# targetboard2.net
KiCad netlist of a schematic drawn in EAGLE
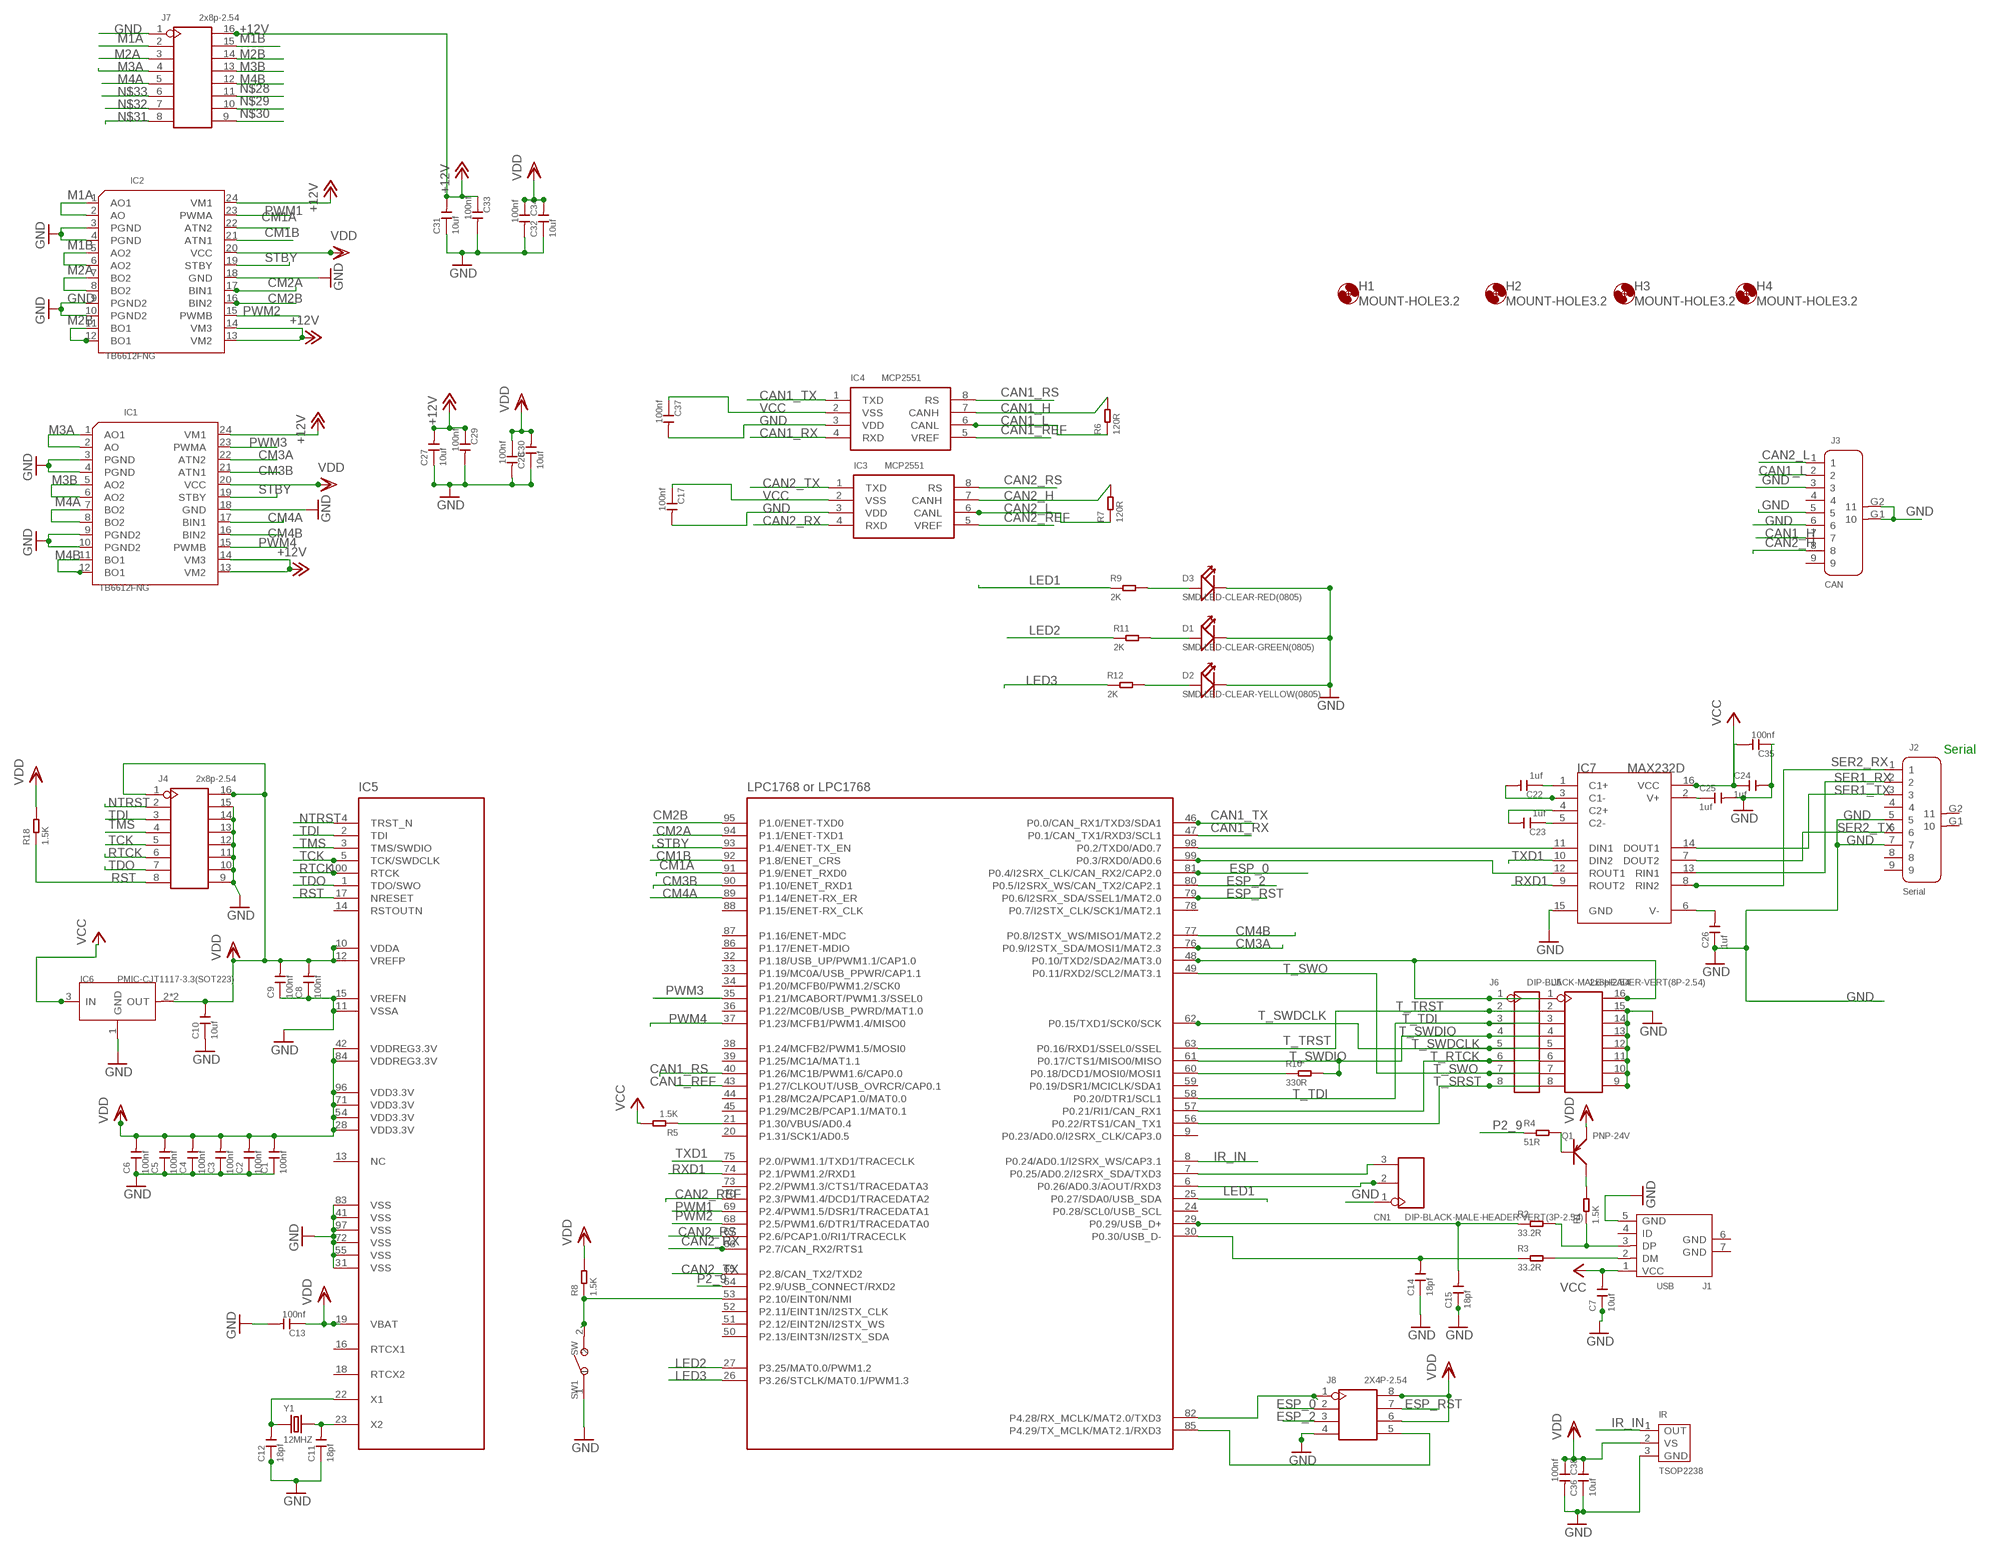
[diagram p0: schematic, sheet 1]

(export (version "E")
  (design (tool "Eeschema 10.0.6"))
  (components
    (comp (ref "C1")
      (value "100nf")
      (footprint "eagle-import:C0805")
      (fields (field (name "MPN") "CC0805KRX7R9BB104"))
      (libsource (lib "eagle-import") (part "CERAMIC-100NF-50V-10%-X7R(0805)"))
    )
    (comp (ref "C2")
      (value "100nf")
      (footprint "eagle-import:C0805")
      (fields (field (name "MPN") "CC0805KRX7R9BB104"))
      (libsource (lib "eagle-import") (part "CERAMIC-100NF-50V-10%-X7R(0805)"))
    )
    (comp (ref "C3")
      (value "100nf")
      (footprint "eagle-import:C0805")
      (fields (field (name "MPN") "CC0805KRX7R9BB104"))
      (libsource (lib "eagle-import") (part "CERAMIC-100NF-50V-10%-X7R(0805)"))
    )
    (comp (ref "C4")
      (value "100nf")
      (footprint "eagle-import:C0805")
      (fields (field (name "MPN") "CC0805KRX7R9BB104"))
      (libsource (lib "eagle-import") (part "CERAMIC-100NF-50V-10%-X7R(0805)"))
    )
    (comp (ref "C5")
      (value "100nf")
      (footprint "eagle-import:C0805")
      (fields (field (name "MPN") "CC0805KRX7R9BB104"))
      (libsource (lib "eagle-import") (part "CERAMIC-100NF-50V-10%-X7R(0805)"))
    )
    (comp (ref "C6")
      (value "100nf")
      (footprint "eagle-import:C0805")
      (fields (field (name "MPN") "CC0805KRX7R9BB104"))
      (libsource (lib "eagle-import") (part "CERAMIC-100NF-50V-10%-X7R(0805)"))
    )
    (comp (ref "C7")
      (value "10uf")
      (footprint "eagle-import:C0603")
      (fields (field (name "MPN") "CC0603KRX5R6BB106"))
      (libsource (lib "eagle-import") (part "CERAMIC-10UF-10V-10%-X5R(0603)"))
    )
    (comp (ref "C8")
      (value "100nf")
      (footprint "eagle-import:C0805")
      (fields (field (name "MPN") "CC0805KRX7R9BB104"))
      (libsource (lib "eagle-import") (part "CERAMIC-100NF-50V-10%-X7R(0805)"))
    )
    (comp (ref "C9")
      (value "100nf")
      (footprint "eagle-import:C0805")
      (fields (field (name "MPN") "CC0805KRX7R9BB104"))
      (libsource (lib "eagle-import") (part "CERAMIC-100NF-50V-10%-X7R(0805)"))
    )
    (comp (ref "C10")
      (value "10uf")
      (footprint "eagle-import:C0805")
      (fields (field (name "MPN") "CC0805KKX5R8BB106"))
      (libsource (lib "eagle-import") (part "CERAMIC-10UF-25V-10%-X5R(0805)"))
    )
    (comp (ref "C11")
      (value "18pf")
      (footprint "eagle-import:C0805")
      (libsource (lib "eagle-import") (part "CERAMIC-18PF-50V-5%-NPO(0805)"))
    )
    (comp (ref "C12")
      (value "18pf")
      (footprint "eagle-import:C0805")
      (libsource (lib "eagle-import") (part "CERAMIC-18PF-50V-5%-NPO(0805)"))
    )
    (comp (ref "C13")
      (value "100nf")
      (footprint "eagle-import:C0805")
      (fields (field (name "MPN") "CC0805KRX7R9BB104"))
      (libsource (lib "eagle-import") (part "CERAMIC-100NF-50V-10%-X7R(0805)"))
    )
    (comp (ref "C14")
      (value "18pf")
      (footprint "eagle-import:C0805")
      (libsource (lib "eagle-import") (part "CERAMIC-18PF-50V-5%-NPO(0805)"))
    )
    (comp (ref "C15")
      (value "18pf")
      (footprint "eagle-import:C0805")
      (libsource (lib "eagle-import") (part "CERAMIC-18PF-50V-5%-NPO(0805)"))
    )
    (comp (ref "C17")
      (value "100nf")
      (footprint "eagle-import:C0805")
      (fields (field (name "MPN") "CC0805KRX7R9BB104"))
      (libsource (lib "eagle-import") (part "CERAMIC-100NF-50V-10%-X7R(0805)"))
    )
    (comp (ref "C22")
      (value "1uf")
      (footprint "eagle-import:C0805")
      (fields (field (name "MPN") "CC0805KKX7R8BB105"))
      (libsource (lib "eagle-import") (part "CERAMIC-1UF-25V-10%-X7R(0805)"))
    )
    (comp (ref "C23")
      (value "1uf")
      (footprint "eagle-import:C0805")
      (fields (field (name "MPN") "CC0805KKX7R8BB105"))
      (libsource (lib "eagle-import") (part "CERAMIC-1UF-25V-10%-X7R(0805)"))
    )
    (comp (ref "C24")
      (value "1uf")
      (footprint "eagle-import:C0805")
      (fields (field (name "MPN") "CC0805KKX7R8BB105"))
      (libsource (lib "eagle-import") (part "CERAMIC-1UF-25V-10%-X7R(0805)"))
    )
    (comp (ref "C25")
      (value "1uf")
      (footprint "eagle-import:C0805")
      (fields (field (name "MPN") "CC0805KKX7R8BB105"))
      (libsource (lib "eagle-import") (part "CERAMIC-1UF-25V-10%-X7R(0805)"))
    )
    (comp (ref "C26")
      (value "1uf")
      (footprint "eagle-import:C0805")
      (fields (field (name "MPN") "CC0805KKX7R8BB105"))
      (libsource (lib "eagle-import") (part "CERAMIC-1UF-25V-10%-X7R(0805)"))
    )
    (comp (ref "C27")
      (value "10uf")
      (footprint "eagle-import:C0805")
      (fields (field (name "MPN") "CC0805KKX5R8BB106"))
      (libsource (lib "eagle-import") (part "CERAMIC-10UF-25V-10%-X5R(0805)"))
    )
    (comp (ref "C28")
      (value "10uf")
      (footprint "eagle-import:C0805")
      (fields (field (name "MPN") "CC0805KKX5R8BB106"))
      (libsource (lib "eagle-import") (part "CERAMIC-10UF-25V-10%-X5R(0805)"))
    )
    (comp (ref "C29")
      (value "100nf")
      (footprint "eagle-import:C0805")
      (fields (field (name "MPN") "CC0805KRX7R9BB104"))
      (libsource (lib "eagle-import") (part "CERAMIC-100NF-50V-10%-X7R(0805)"))
    )
    (comp (ref "C30")
      (value "100nf")
      (footprint "eagle-import:C0805")
      (fields (field (name "MPN") "CC0805KRX7R9BB104"))
      (libsource (lib "eagle-import") (part "CERAMIC-100NF-50V-10%-X7R(0805)"))
    )
    (comp (ref "C31")
      (value "10uf")
      (footprint "eagle-import:C0805")
      (fields (field (name "MPN") "CC0805KKX5R8BB106"))
      (libsource (lib "eagle-import") (part "CERAMIC-10UF-25V-10%-X5R(0805)"))
    )
    (comp (ref "C32")
      (value "10uf")
      (footprint "eagle-import:C0805")
      (fields (field (name "MPN") "CC0805KKX5R8BB106"))
      (libsource (lib "eagle-import") (part "CERAMIC-10UF-25V-10%-X5R(0805)"))
    )
    (comp (ref "C33")
      (value "100nf")
      (footprint "eagle-import:C0805")
      (fields (field (name "MPN") "CC0805KRX7R9BB104"))
      (libsource (lib "eagle-import") (part "CERAMIC-100NF-50V-10%-X7R(0805)"))
    )
    (comp (ref "C34")
      (value "100nf")
      (footprint "eagle-import:C0805")
      (fields (field (name "MPN") "CC0805KRX7R9BB104"))
      (libsource (lib "eagle-import") (part "CERAMIC-100NF-50V-10%-X7R(0805)"))
    )
    (comp (ref "C35")
      (value "100nf")
      (footprint "eagle-import:C0805")
      (fields (field (name "MPN") "CC0805KRX7R9BB104"))
      (libsource (lib "eagle-import") (part "CERAMIC-100NF-50V-10%-X7R(0805)"))
    )
    (comp (ref "C36")
      (value "10uf")
      (footprint "eagle-import:C0805")
      (fields (field (name "MPN") "CC0805KKX5R8BB106"))
      (libsource (lib "eagle-import") (part "CERAMIC-10UF-25V-10%-X5R(0805)"))
    )
    (comp (ref "C37")
      (value "100nf")
      (footprint "eagle-import:C0805")
      (fields (field (name "MPN") "CC0805KRX7R9BB104"))
      (libsource (lib "eagle-import") (part "CERAMIC-100NF-50V-10%-X7R(0805)"))
    )
    (comp (ref "C38")
      (value "100nf")
      (footprint "eagle-import:C0805")
      (fields (field (name "MPN") "CC0805KRX7R9BB104"))
      (libsource (lib "eagle-import") (part "CERAMIC-100NF-50V-10%-X7R(0805)"))
    )
    (comp (ref "CN1")
      (value "DIP-BLACK-MALE-HEADER-VERT(3P-2.54)")
      (footprint "eagle-import:H3-2.54")
      (libsource (lib "eagle-import") (part "DIP-BLACK-MALE-HEADER-VERT(3P-2.54)"))
    )
    (comp (ref "D1")
      (value "SMD-LED-CLEAR-GREEN(0805)")
      (footprint "eagle-import:LED-0805")
      (fields (field (name "MPN") "17-215SYGC/S530-E2/TR8"))
      (libsource (lib "eagle-import") (part "SMD-LED-CLEAR-GREEN(0805)"))
    )
    (comp (ref "D2")
      (value "SMD-LED-CLEAR-YELLOW(0805)")
      (footprint "eagle-import:LED-0805")
      (fields (field (name "MPN") "17-215UYC/S530-A3/TR8"))
      (libsource (lib "eagle-import") (part "SMD-LED-CLEAR-YELLOW(0805)"))
    )
    (comp (ref "D3")
      (value "SMD-LED-CLEAR-RED(0805)")
      (footprint "eagle-import:LED-0805")
      (fields (field (name "MPN") "17-215SURC/S530-A2/TR8"))
      (libsource (lib "eagle-import") (part "SMD-LED-CLEAR-RED(0805)"))
    )
    (comp (ref "H1")
      (value "MOUNT-HOLE3.2")
      (footprint "eagle-import:3,2")
      (libsource (lib "eagle-import") (part "MOUNT-HOLE3.2"))
    )
    (comp (ref "H2")
      (value "MOUNT-HOLE3.2")
      (footprint "eagle-import:3,2")
      (libsource (lib "eagle-import") (part "MOUNT-HOLE3.2"))
    )
    (comp (ref "H3")
      (value "MOUNT-HOLE3.2")
      (footprint "eagle-import:3,2")
      (libsource (lib "eagle-import") (part "MOUNT-HOLE3.2"))
    )
    (comp (ref "H4")
      (value "MOUNT-HOLE3.2")
      (footprint "eagle-import:3,2")
      (libsource (lib "eagle-import") (part "MOUNT-HOLE3.2"))
    )
    (comp (ref "IC1")
      (value "TB6612FNG")
      (footprint "eagle-import:SSOP24-0.65-8.9X5.3MM")
      (fields (field (name "MPN") "TB6612FNG-O/C8/EL"))
      (libsource (lib "eagle-import") (part "DRIVER-TB6612FNG-O/C8/EL(SSOP24)"))
    )
    (comp (ref "IC2")
      (value "TB6612FNG")
      (footprint "eagle-import:SSOP24-0.65-8.9X5.3MM")
      (fields (field (name "MPN") "TB6612FNG-O/C8/EL"))
      (libsource (lib "eagle-import") (part "DRIVER-TB6612FNG-O/C8/EL(SSOP24)"))
    )
    (comp (ref "IC3")
      (value "MCP2551")
      (footprint "eagle-import:SOIC8-1.27-5X4MM")
      (fields (field (name "MPN") "MCP2551-I/SN"))
      (libsource (lib "eagle-import") (part "INTERFACE-MCP2551-I/SN(SOIC8)"))
    )
    (comp (ref "IC4")
      (value "MCP2551")
      (footprint "eagle-import:SOIC8-1.27-5X4MM")
      (fields (field (name "MPN") "MCP2551-I/SN"))
      (libsource (lib "eagle-import") (part "INTERFACE-MCP2551-I/SN(SOIC8)"))
    )
    (comp (ref "IC5")
      (value "LPC1768 or LPC1768")
      (footprint "eagle-import:LQFP100-0.5-13.8X13.8MM")
      (fields (field (name "MPN") "LPC1768FBD100"))
      (libsource (lib "eagle-import") (part "MCU_LPC1768FBD100(LQFP100)"))
    )
    (comp (ref "IC6")
      (value "PMIC-CJT1117-3.3(SOT223)")
      (footprint "eagle-import:SOT-223")
      (fields (field (name "MPN") "CJT1117-3.3"))
      (libsource (lib "eagle-import") (part "PMIC-CJT1117-3.3(SOT223)"))
    )
    (comp (ref "IC7")
      (value "MAX232D")
      (footprint "eagle-import:SOIC16-1.27-10X3.9MM")
      (libsource (lib "eagle-import") (part "RECEIVER-MAX232D(SOIC16)"))
    )
    (comp (ref "IR")
      (value "TSOP2238")
      (footprint "eagle-import:SNR3-2.54-6.95X6.0X5.6MM")
      (libsource (lib "eagle-import") (part "OPTICAL-TSOP2238"))
    )
    (comp (ref "J1")
      (value "USB")
      (footprint "eagle-import:MICRO-USB5+2P-SMD-0.65")
      (fields (field (name "MPN") "ST-USB-001L"))
      (libsource (lib "eagle-import") (part "MICRO-USB-SMD-TYPE-AB-R/A(ST-USB-001L)"))
    )
    (comp (ref "J2")
      (value "Serial")
      (footprint "eagle-import:DSUB9+2P-2.77-90D-MALE")
      (libsource (lib "eagle-import") (part "DIP-MALE-DB9-CONNECTOR"))
    )
    (comp (ref "J3")
      (value "CAN")
      (footprint "eagle-import:DSUB9+2P-2.77-90D-MALE")
      (libsource (lib "eagle-import") (part "DIP-MALE-DB9-CONNECTOR"))
    )
    (comp (ref "J4")
      (value "2x8p-2.54")
      (footprint "eagle-import:H2X8-2.54")
      (fields (field (name "MPN") "P125-1216A0AS116A1"))
      (libsource (lib "eagle-import") (part "DIP-BLACK-MALE-HEADER-VERT(2X8P-2.54)"))
    )
    (comp (ref "J5")
      (value "2x8p-2.54")
      (footprint "eagle-import:H2X8-2.54")
      (fields (field (name "MPN") "P125-1216A0AS116A1"))
      (libsource (lib "eagle-import") (part "DIP-BLACK-MALE-HEADER-VERT(2X8P-2.54)"))
    )
    (comp (ref "J6")
      (value "DIP-BLACK-MALE-HEADER-VERT(8P-2.54)")
      (footprint "eagle-import:H8-2.54")
      (fields (field (name "MPN") "P125-1108A1BS116A1"))
      (libsource (lib "eagle-import") (part "DIP-BLACK-MALE-HEADER-VERT(8P-2.54)"))
    )
    (comp (ref "J7")
      (value "2x8p-2.54")
      (footprint "eagle-import:H2X8-2.54")
      (fields (field (name "MPN") "P125-1216A0AS116A1"))
      (libsource (lib "eagle-import") (part "DIP-BLACK-MALE-HEADER-VERT(2X8P-2.54)"))
    )
    (comp (ref "J8")
      (value "2X4P-2.54")
      (footprint "eagle-import:H2X4-2.54")
      (libsource (lib "eagle-import") (part "DIP-BLACK-FEMALE-HEADER(2X4P-2.54)"))
    )
    (comp (ref "Q1")
      (value "PNP-24V")
      (footprint "eagle-import:SOT-23")
      (fields (field (name "MPN") "S8550"))
      (libsource (lib "eagle-import") (part "SMD-TRANSISTORS-PNP-25V-500MA(SOT-23)"))
    )
    (comp (ref "R1")
      (value "1.5K")
      (footprint "eagle-import:R0402")
      (fields (field (name "MPN") "RC0402JR-071K5L"))
      (libsource (lib "eagle-import") (part "SMD-RES-1.5K-5%-1/16W(0402)"))
    )
    (comp (ref "R2")
      (value "33.2R")
      (footprint "eagle-import:R0603")
      (fields (field (name "MPN") "RC0603FR-0733R2L"))
      (libsource (lib "eagle-import") (part "SMD-RES-33.2R-1%-1/10W(0603)"))
    )
    (comp (ref "R3")
      (value "33.2R")
      (footprint "eagle-import:R0603")
      (fields (field (name "MPN") "RC0603FR-0733R2L"))
      (libsource (lib "eagle-import") (part "SMD-RES-33.2R-1%-1/10W(0603)"))
    )
    (comp (ref "R4")
      (value "51R")
      (footprint "eagle-import:R0603")
      (fields (field (name "MPN") "RC0603FR-0751RL"))
      (libsource (lib "eagle-import") (part "SMD-RES-51R-1%-1/10W(0603)"))
    )
    (comp (ref "R5")
      (value "1.5K")
      (footprint "eagle-import:R0402")
      (fields (field (name "MPN") "RC0402JR-071K5L"))
      (libsource (lib "eagle-import") (part "SMD-RES-1.5K-5%-1/16W(0402)"))
    )
    (comp (ref "R6")
      (value "120R")
      (footprint "eagle-import:R0805")
      (fields (field (name "MPN") "RC0805JR-07120RL"))
      (libsource (lib "eagle-import") (part "SMD-RES-120R-5%-1/8W(0805)"))
    )
    (comp (ref "R7")
      (value "120R")
      (footprint "eagle-import:R0805")
      (fields (field (name "MPN") "RC0805JR-07120RL"))
      (libsource (lib "eagle-import") (part "SMD-RES-120R-5%-1/8W(0805)"))
    )
    (comp (ref "R8")
      (value "1.5K")
      (footprint "eagle-import:R0402")
      (fields (field (name "MPN") "RC0402JR-071K5L"))
      (libsource (lib "eagle-import") (part "SMD-RES-1.5K-5%-1/16W(0402)"))
    )
    (comp (ref "R9")
      (value "2K")
      (footprint "eagle-import:R0805")
      (fields (field (name "MPN") "RC0805JR-072KL"))
      (libsource (lib "eagle-import") (part "SMD-RES-2K-5%-1/8W(0805)"))
    )
    (comp (ref "R10")
      (value "330R")
      (footprint "eagle-import:R0603")
      (fields (field (name "MPN") "RC0603FR-07330RL"))
      (libsource (lib "eagle-import") (part "SMD-RES-330R-1%-1/10W(0603)"))
    )
    (comp (ref "R11")
      (value "2K")
      (footprint "eagle-import:R0805")
      (fields (field (name "MPN") "RC0805JR-072KL"))
      (libsource (lib "eagle-import") (part "SMD-RES-2K-5%-1/8W(0805)"))
    )
    (comp (ref "R12")
      (value "2K")
      (footprint "eagle-import:R0805")
      (fields (field (name "MPN") "RC0805JR-072KL"))
      (libsource (lib "eagle-import") (part "SMD-RES-2K-5%-1/8W(0805)"))
    )
    (comp (ref "R18")
      (value "1.5K")
      (footprint "eagle-import:R0402")
      (fields (field (name "MPN") "RC0402JR-071K5L"))
      (libsource (lib "eagle-import") (part "SMD-RES-1.5K-5%-1/16W(0402)"))
    )
    (comp (ref "SW1")
      (value "SW")
      (footprint "eagle-import:SW2-2.6-3.0X2.5X1.2+0.4MM")
      (libsource (lib "eagle-import") (part "SMD-BUTTON(2P-3.0X2.5X1.2+0.4MM)-B3U-1000P-2P-SMD"))
    )
    (comp (ref "Y1")
      (value "12MHZ")
      (footprint "eagle-import:X2-SMD-5.0X3.2X1.3MM")
      (fields (field (name "MPN") "5032/2P"))
      (libsource (lib "eagle-import") (part "SMD-CRYSTAL-12MHZ-20PF-20PPM-40R(2P-5.0X3.2MM)"))
    )
  )
  (nets
    (net (code "1") (name "+12V") (class "Default")
      (node (ref "C27") (pin "2") (pinfunction "2_2") (pintype "passive"))
      (node (ref "C29") (pin "1") (pinfunction "1_1") (pintype "passive"))
      (node (ref "C31") (pin "2") (pinfunction "2_2") (pintype "passive"))
      (node (ref "C33") (pin "1") (pinfunction "1_1") (pintype "passive"))
      (node (ref "IC1") (pin "13") (pinfunction "VM2_13") (pintype "bidirectional"))
      (node (ref "IC1") (pin "14") (pinfunction "VM3_14") (pintype "bidirectional"))
      (node (ref "IC1") (pin "24") (pinfunction "VM1_24") (pintype "bidirectional"))
      (node (ref "IC2") (pin "13") (pinfunction "VM2_13") (pintype "bidirectional"))
      (node (ref "IC2") (pin "14") (pinfunction "VM3_14") (pintype "bidirectional"))
      (node (ref "IC2") (pin "24") (pinfunction "VM1_24") (pintype "bidirectional"))
      (node (ref "J7") (pin "16") (pinfunction "16_16") (pintype "bidirectional"))
    )
    (net (code "2") (name "/CAN1_H") (class "Default")
      (node (ref "IC4") (pin "7") (pinfunction "CANH_7") (pintype "bidirectional"))
      (node (ref "J3") (pin "7") (pinfunction "7_7") (pintype "bidirectional"))
      (node (ref "R6") (pin "2") (pinfunction "2_2") (pintype "passive"))
    )
    (net (code "3") (name "/CAN1_L") (class "Default")
      (node (ref "IC4") (pin "6") (pinfunction "CANL_6") (pintype "bidirectional"))
      (node (ref "J3") (pin "2") (pinfunction "2_2") (pintype "bidirectional"))
      (node (ref "R6") (pin "1") (pinfunction "1_1") (pintype "passive"))
    )
    (net (code "4") (name "/CAN1_REF") (class "Default")
      (node (ref "IC4") (pin "5") (pinfunction "VREF_5") (pintype "bidirectional"))
      (node (ref "IC5") (pin "43") (pinfunction "P1.27/CLKOUT/USB_OVRCR/CAP0.1_43") (pintype "bidirectional"))
    )
    (net (code "5") (name "/CAN1_RS") (class "Default")
      (node (ref "IC4") (pin "8") (pinfunction "RS_8") (pintype "bidirectional"))
      (node (ref "IC5") (pin "40") (pinfunction "P1.26/MC1B/PWM1.6/CAP0.0_40") (pintype "bidirectional"))
    )
    (net (code "6") (name "/CAN1_RX") (class "Default")
      (node (ref "IC4") (pin "4") (pinfunction "RXD_4") (pintype "bidirectional"))
      (node (ref "IC5") (pin "47") (pinfunction "P0.1/CAN_TX1/RXD3/SCL1_47") (pintype "bidirectional"))
    )
    (net (code "7") (name "/CAN1_TX") (class "Default")
      (node (ref "IC4") (pin "1") (pinfunction "TXD_1") (pintype "bidirectional"))
      (node (ref "IC5") (pin "46") (pinfunction "P0.0/CAN_RX1/TXD3/SDA1_46") (pintype "bidirectional"))
    )
    (net (code "8") (name "/CAN2_H") (class "Default")
      (node (ref "IC3") (pin "7") (pinfunction "CANH_7") (pintype "bidirectional"))
      (node (ref "J3") (pin "8") (pinfunction "8_8") (pintype "bidirectional"))
      (node (ref "R7") (pin "2") (pinfunction "2_2") (pintype "passive"))
    )
    (net (code "9") (name "/CAN2_L") (class "Default")
      (node (ref "IC3") (pin "6") (pinfunction "CANL_6") (pintype "bidirectional"))
      (node (ref "J3") (pin "1") (pinfunction "1_1") (pintype "bidirectional"))
      (node (ref "R7") (pin "1") (pinfunction "1_1") (pintype "passive"))
    )
    (net (code "10") (name "/CAN2_REF") (class "Default")
      (node (ref "IC3") (pin "5") (pinfunction "VREF_5") (pintype "bidirectional"))
      (node (ref "IC5") (pin "70") (pinfunction "P2.3/PWM1.4/DCD1/TRACEDATA2_70") (pintype "bidirectional"))
    )
    (net (code "11") (name "/CAN2_RS") (class "Default")
      (node (ref "IC3") (pin "8") (pinfunction "RS_8") (pintype "bidirectional"))
      (node (ref "IC5") (pin "67") (pinfunction "P2.6/PCAP1.0/RI1/TRACECLK_67") (pintype "bidirectional"))
    )
    (net (code "12") (name "/CAN2_RX") (class "Default")
      (node (ref "IC3") (pin "4") (pinfunction "RXD_4") (pintype "bidirectional"))
      (node (ref "IC5") (pin "66") (pinfunction "P2.7/CAN_RX2/RTS1_66") (pintype "bidirectional"))
    )
    (net (code "13") (name "/CAN2_TX") (class "Default")
      (node (ref "IC3") (pin "1") (pinfunction "TXD_1") (pintype "bidirectional"))
      (node (ref "IC5") (pin "65") (pinfunction "P2.8/CAN_TX2/TXD2_65") (pintype "bidirectional"))
    )
    (net (code "14") (name "/CM1A") (class "Default")
      (node (ref "IC2") (pin "22") (pinfunction "ATN2_22") (pintype "bidirectional"))
      (node (ref "IC5") (pin "91") (pinfunction "P1.9/ENET_RXD0_91") (pintype "bidirectional"))
    )
    (net (code "15") (name "/CM1B") (class "Default")
      (node (ref "IC2") (pin "21") (pinfunction "ATN1_21") (pintype "bidirectional"))
      (node (ref "IC5") (pin "92") (pinfunction "P1.8/ENET_CRS_92") (pintype "bidirectional"))
    )
    (net (code "16") (name "/CM2A") (class "Default")
      (node (ref "IC2") (pin "17") (pinfunction "BIN1_17") (pintype "bidirectional"))
      (node (ref "IC5") (pin "94") (pinfunction "P1.1/ENET-TXD1_94") (pintype "bidirectional"))
    )
    (net (code "17") (name "/CM2B") (class "Default")
      (node (ref "IC2") (pin "16") (pinfunction "BIN2_16") (pintype "bidirectional"))
      (node (ref "IC5") (pin "95") (pinfunction "P1.0/ENET-TXD0_95") (pintype "bidirectional"))
    )
    (net (code "18") (name "/CM3A") (class "Default")
      (node (ref "IC1") (pin "22") (pinfunction "ATN2_22") (pintype "bidirectional"))
      (node (ref "IC5") (pin "76") (pinfunction "P0.9/I2STX_SDA/MOSI1/MAT2.3_76") (pintype "bidirectional"))
    )
    (net (code "19") (name "/CM3B") (class "Default")
      (node (ref "IC1") (pin "21") (pinfunction "ATN1_21") (pintype "bidirectional"))
      (node (ref "IC5") (pin "90") (pinfunction "P1.10/ENET_RXD1_90") (pintype "bidirectional"))
    )
    (net (code "20") (name "/CM4A") (class "Default")
      (node (ref "IC1") (pin "17") (pinfunction "BIN1_17") (pintype "bidirectional"))
      (node (ref "IC5") (pin "89") (pinfunction "P1.14/ENET-RX_ER_89") (pintype "bidirectional"))
    )
    (net (code "21") (name "/CM4B") (class "Default")
      (node (ref "IC1") (pin "16") (pinfunction "BIN2_16") (pintype "bidirectional"))
      (node (ref "IC5") (pin "77") (pinfunction "P0.8/I2STX_WS/MISO1/MAT2.2_77") (pintype "bidirectional"))
    )
    (net (code "22") (name "/ESP_0") (class "Default")
      (node (ref "IC5") (pin "81") (pinfunction "P0.4/I2SRX_CLK/CAN_RX2/CAP2.0_81") (pintype "bidirectional"))
      (node (ref "J8") (pin "2") (pinfunction "2_2") (pintype "bidirectional"))
    )
    (net (code "23") (name "/ESP_2") (class "Default")
      (node (ref "IC5") (pin "80") (pinfunction "P0.5/I2SRX_WS/CAN_TX2/CAP2.1_80") (pintype "bidirectional"))
      (node (ref "J8") (pin "3") (pinfunction "3_3") (pintype "bidirectional"))
    )
    (net (code "24") (name "/ESP_RST") (class "Default")
      (node (ref "IC5") (pin "79") (pinfunction "P0.6/I2SRX_SDA/SSEL1/MAT2.0_79") (pintype "bidirectional"))
      (node (ref "J8") (pin "7") (pinfunction "7_7") (pintype "bidirectional"))
    )
    (net (code "25") (name "/IR_IN") (class "Default")
      (node (ref "IC5") (pin "8") (pinfunction "P0.24/AD0.1/I2SRX_WS/CAP3.1_8") (pintype "bidirectional"))
      (node (ref "IR") (pin "1") (pinfunction "OUT_1") (pintype "bidirectional"))
    )
    (net (code "26") (name "/LED1") (class "Default")
      (node (ref "IC5") (pin "25") (pinfunction "P0.27/SDA0/USB_SDA_25") (pintype "bidirectional"))
      (node (ref "R9") (pin "1") (pinfunction "1_1") (pintype "passive"))
    )
    (net (code "27") (name "/LED2") (class "Default")
      (node (ref "IC5") (pin "27") (pinfunction "P3.25/MAT0.0/PWM1.2_27") (pintype "bidirectional"))
      (node (ref "R11") (pin "1") (pinfunction "1_1") (pintype "passive"))
    )
    (net (code "28") (name "/LED3") (class "Default")
      (node (ref "IC5") (pin "26") (pinfunction "P3.26/STCLK/MAT0.1/PWM1.3_26") (pintype "bidirectional"))
      (node (ref "R12") (pin "1") (pinfunction "1_1") (pintype "passive"))
    )
    (net (code "29") (name "/M1A") (class "Default")
      (node (ref "IC2") (pin "1") (pinfunction "AO1_1") (pintype "bidirectional"))
      (node (ref "IC2") (pin "2") (pinfunction "AO_2") (pintype "bidirectional"))
      (node (ref "J7") (pin "2") (pinfunction "2_2") (pintype "bidirectional"))
    )
    (net (code "30") (name "/M1B") (class "Default")
      (node (ref "IC2") (pin "5") (pinfunction "AO2_5") (pintype "bidirectional"))
      (node (ref "IC2") (pin "6") (pinfunction "AO2_6") (pintype "bidirectional"))
      (node (ref "J7") (pin "15") (pinfunction "15_15") (pintype "bidirectional"))
    )
    (net (code "31") (name "/M2A") (class "Default")
      (node (ref "IC2") (pin "7") (pinfunction "BO2_7") (pintype "bidirectional"))
      (node (ref "IC2") (pin "8") (pinfunction "BO2_8") (pintype "bidirectional"))
      (node (ref "J7") (pin "3") (pinfunction "3_3") (pintype "bidirectional"))
    )
    (net (code "32") (name "/M2B") (class "Default")
      (node (ref "IC2") (pin "11") (pinfunction "BO1_11") (pintype "bidirectional"))
      (node (ref "IC2") (pin "12") (pinfunction "BO1_12") (pintype "bidirectional"))
      (node (ref "J7") (pin "14") (pinfunction "14_14") (pintype "bidirectional"))
    )
    (net (code "33") (name "/M3A") (class "Default")
      (node (ref "IC1") (pin "1") (pinfunction "AO1_1") (pintype "bidirectional"))
      (node (ref "IC1") (pin "2") (pinfunction "AO_2") (pintype "bidirectional"))
      (node (ref "J7") (pin "4") (pinfunction "4_4") (pintype "bidirectional"))
    )
    (net (code "34") (name "/M3B") (class "Default")
      (node (ref "IC1") (pin "5") (pinfunction "AO2_5") (pintype "bidirectional"))
      (node (ref "IC1") (pin "6") (pinfunction "AO2_6") (pintype "bidirectional"))
      (node (ref "J7") (pin "13") (pinfunction "13_13") (pintype "bidirectional"))
    )
    (net (code "35") (name "/M4A") (class "Default")
      (node (ref "IC1") (pin "7") (pinfunction "BO2_7") (pintype "bidirectional"))
      (node (ref "IC1") (pin "8") (pinfunction "BO2_8") (pintype "bidirectional"))
      (node (ref "J7") (pin "5") (pinfunction "5_5") (pintype "bidirectional"))
    )
    (net (code "36") (name "/M4B") (class "Default")
      (node (ref "IC1") (pin "11") (pinfunction "BO1_11") (pintype "bidirectional"))
      (node (ref "IC1") (pin "12") (pinfunction "BO1_12") (pintype "bidirectional"))
      (node (ref "J7") (pin "12") (pinfunction "12_12") (pintype "bidirectional"))
    )
    (net (code "37") (name "/N$28") (class "Default")
      (node (ref "J7") (pin "11") (pinfunction "11_11") (pintype "bidirectional"))
    )
    (net (code "38") (name "/N$29") (class "Default")
      (node (ref "J7") (pin "10") (pinfunction "10_10") (pintype "bidirectional"))
    )
    (net (code "39") (name "/N$30") (class "Default")
      (node (ref "J7") (pin "9") (pinfunction "9_9") (pintype "bidirectional"))
    )
    (net (code "40") (name "/N$31") (class "Default")
      (node (ref "J7") (pin "8") (pinfunction "8_8") (pintype "bidirectional"))
    )
    (net (code "41") (name "/N$32") (class "Default")
      (node (ref "J7") (pin "7") (pinfunction "7_7") (pintype "bidirectional"))
    )
    (net (code "42") (name "/N$33") (class "Default")
      (node (ref "J7") (pin "6") (pinfunction "6_6") (pintype "bidirectional"))
    )
    (net (code "43") (name "/NTRST") (class "Default")
      (node (ref "IC5") (pin "4") (pinfunction "TRST_N_4") (pintype "bidirectional"))
      (node (ref "J4") (pin "2") (pinfunction "2_2") (pintype "bidirectional"))
    )
    (net (code "44") (name "/P2_9") (class "Default")
      (node (ref "IC5") (pin "64") (pinfunction "P2.9/USB_CONNECT/RXD2_64") (pintype "bidirectional"))
      (node (ref "R4") (pin "1") (pinfunction "1_1") (pintype "passive"))
    )
    (net (code "45") (name "/PWM1") (class "Default")
      (node (ref "IC2") (pin "23") (pinfunction "PWMA_23") (pintype "bidirectional"))
      (node (ref "IC5") (pin "69") (pinfunction "P2.4/PWM1.5/DSR1/TRACEDATA1_69") (pintype "bidirectional"))
    )
    (net (code "46") (name "/PWM2") (class "Default")
      (node (ref "IC2") (pin "15") (pinfunction "PWMB_15") (pintype "bidirectional"))
      (node (ref "IC5") (pin "68") (pinfunction "P2.5/PWM1.6/DTR1/TRACEDATA0_68") (pintype "bidirectional"))
    )
    (net (code "47") (name "/PWM3") (class "Default")
      (node (ref "IC1") (pin "23") (pinfunction "PWMA_23") (pintype "bidirectional"))
      (node (ref "IC5") (pin "35") (pinfunction "P1.21/MCABORT/PWM1.3/SSEL0_35") (pintype "bidirectional"))
    )
    (net (code "48") (name "/PWM4") (class "Default")
      (node (ref "IC1") (pin "15") (pinfunction "PWMB_15") (pintype "bidirectional"))
      (node (ref "IC5") (pin "37") (pinfunction "P1.23/MCFB1/PWM1.4/MISO0_37") (pintype "bidirectional"))
    )
    (net (code "49") (name "/RST") (class "Default")
      (node (ref "IC5") (pin "17") (pinfunction "NRESET_17") (pintype "bidirectional"))
      (node (ref "J4") (pin "8") (pinfunction "8_8") (pintype "bidirectional"))
      (node (ref "R18") (pin "1") (pinfunction "1_1") (pintype "passive"))
    )
    (net (code "50") (name "/RTCK") (class "Default")
      (node (ref "IC5") (pin "100") (pinfunction "RTCK_100") (pintype "bidirectional"))
      (node (ref "J4") (pin "6") (pinfunction "6_6") (pintype "bidirectional"))
    )
    (net (code "51") (name "/RXD1") (class "Default")
      (node (ref "IC5") (pin "74") (pinfunction "P2.1/PWM1.2/RXD1_74") (pintype "bidirectional"))
      (node (ref "IC7") (pin "9") (pinfunction "ROUT2_9") (pintype "bidirectional"))
    )
    (net (code "52") (name "/SER1_RX") (class "Default")
      (node (ref "IC7") (pin "13") (pinfunction "RIN1_13") (pintype "bidirectional"))
      (node (ref "J2") (pin "2") (pinfunction "2_2") (pintype "bidirectional"))
    )
    (net (code "53") (name "/SER1_TX") (class "Default")
      (node (ref "IC7") (pin "14") (pinfunction "DOUT1_14") (pintype "bidirectional"))
      (node (ref "J2") (pin "3") (pinfunction "3_3") (pintype "bidirectional"))
    )
    (net (code "54") (name "/SER2_RX") (class "Default")
      (node (ref "IC7") (pin "8") (pinfunction "RIN2_8") (pintype "bidirectional"))
      (node (ref "J2") (pin "1") (pinfunction "1_1") (pintype "bidirectional"))
    )
    (net (code "55") (name "/SER2_TX") (class "Default")
      (node (ref "IC7") (pin "7") (pinfunction "DOUT2_7") (pintype "bidirectional"))
      (node (ref "J2") (pin "6") (pinfunction "6_6") (pintype "bidirectional"))
    )
    (net (code "56") (name "/STBY") (class "Default")
      (node (ref "IC1") (pin "19") (pinfunction "STBY_19") (pintype "bidirectional"))
      (node (ref "IC2") (pin "19") (pinfunction "STBY_19") (pintype "bidirectional"))
      (node (ref "IC5") (pin "93") (pinfunction "P1.4/ENET-TX_EN_93") (pintype "bidirectional"))
    )
    (net (code "57") (name "/TCK") (class "Default")
      (node (ref "IC5") (pin "5") (pinfunction "TCK/SWDCLK_5") (pintype "bidirectional"))
      (node (ref "J4") (pin "5") (pinfunction "5_5") (pintype "bidirectional"))
    )
    (net (code "58") (name "/TDI") (class "Default")
      (node (ref "IC5") (pin "2") (pinfunction "TDI_2") (pintype "bidirectional"))
      (node (ref "J4") (pin "3") (pinfunction "3_3") (pintype "bidirectional"))
    )
    (net (code "59") (name "/TDO") (class "Default")
      (node (ref "IC5") (pin "1") (pinfunction "TDO/SWO_1") (pintype "bidirectional"))
      (node (ref "J4") (pin "7") (pinfunction "7_7") (pintype "bidirectional"))
    )
    (net (code "60") (name "/TMS") (class "Default")
      (node (ref "IC5") (pin "3") (pinfunction "TMS/SWDIO_3") (pintype "bidirectional"))
      (node (ref "J4") (pin "4") (pinfunction "4_4") (pintype "bidirectional"))
    )
    (net (code "61") (name "/TXD1") (class "Default")
      (node (ref "IC5") (pin "75") (pinfunction "P2.0/PWM1.1/TXD1/TRACECLK_75") (pintype "bidirectional"))
      (node (ref "IC7") (pin "10") (pinfunction "DIN2_10") (pintype "bidirectional"))
    )
    (net (code "62") (name "/T_RTCK") (class "Default")
      (node (ref "IC5") (pin "57") (pinfunction "P0.21/RI1/CAN_RX1_57") (pintype "bidirectional"))
      (node (ref "J5") (pin "6") (pinfunction "6_6") (pintype "bidirectional"))
      (node (ref "J6") (pin "6") (pinfunction "6_6") (pintype "bidirectional"))
    )
    (net (code "63") (name "/T_SRST") (class "Default")
      (node (ref "IC5") (pin "56") (pinfunction "P0.22/RTS1/CAN_TX1_56") (pintype "bidirectional"))
      (node (ref "J5") (pin "8") (pinfunction "8_8") (pintype "bidirectional"))
      (node (ref "J6") (pin "8") (pinfunction "8_8") (pintype "bidirectional"))
    )
    (net (code "64") (name "/T_SWDCLK") (class "Default")
      (node (ref "IC5") (pin "62") (pinfunction "P0.15/TXD1/SCK0/SCK_62") (pintype "bidirectional"))
      (node (ref "J5") (pin "5") (pinfunction "5_5") (pintype "bidirectional"))
      (node (ref "J6") (pin "5") (pinfunction "5_5") (pintype "bidirectional"))
    )
    (net (code "65") (name "/T_SWDIO") (class "Default")
      (node (ref "IC5") (pin "61") (pinfunction "P0.17/CTS1/MISO0/MISO_61") (pintype "bidirectional"))
      (node (ref "J5") (pin "4") (pinfunction "4_4") (pintype "bidirectional"))
      (node (ref "J6") (pin "4") (pinfunction "4_4") (pintype "bidirectional"))
      (node (ref "R10") (pin "2") (pinfunction "2_2") (pintype "passive"))
    )
    (net (code "66") (name "/T_SWO") (class "Default")
      (node (ref "IC5") (pin "49") (pinfunction "P0.11/RXD2/SCL2/MAT3.1_49") (pintype "bidirectional"))
      (node (ref "J5") (pin "7") (pinfunction "7_7") (pintype "bidirectional"))
      (node (ref "J6") (pin "7") (pinfunction "7_7") (pintype "bidirectional"))
    )
    (net (code "67") (name "/T_TDI") (class "Default")
      (node (ref "IC5") (pin "58") (pinfunction "P0.20/DTR1/SCL1_58") (pintype "bidirectional"))
      (node (ref "J5") (pin "3") (pinfunction "3_3") (pintype "bidirectional"))
      (node (ref "J6") (pin "3") (pinfunction "3_3") (pintype "bidirectional"))
    )
    (net (code "68") (name "/T_TRST") (class "Default")
      (node (ref "IC5") (pin "63") (pinfunction "P0.16/RXD1/SSEL0/SSEL_63") (pintype "bidirectional"))
      (node (ref "J5") (pin "2") (pinfunction "2_2") (pintype "bidirectional"))
      (node (ref "J6") (pin "2") (pinfunction "2_2") (pintype "bidirectional"))
    )
    (net (code "69") (name "GND") (class "Default")
      (node (ref "C1") (pin "1") (pinfunction "1_1") (pintype "passive"))
      (node (ref "C10") (pin "1") (pinfunction "1_1") (pintype "passive"))
      (node (ref "C11") (pin "1") (pinfunction "1_1") (pintype "passive"))
      (node (ref "C12") (pin "1") (pinfunction "1_1") (pintype "passive"))
      (node (ref "C13") (pin "2") (pinfunction "2_2") (pintype "passive"))
      (node (ref "C14") (pin "1") (pinfunction "1_1") (pintype "passive"))
      (node (ref "C15") (pin "1") (pinfunction "1_1") (pintype "passive"))
      (node (ref "C17") (pin "2") (pinfunction "2_2") (pintype "passive"))
      (node (ref "C2") (pin "1") (pinfunction "1_1") (pintype "passive"))
      (node (ref "C24") (pin "2") (pinfunction "2_2") (pintype "passive"))
      (node (ref "C25") (pin "2") (pinfunction "2_2") (pintype "passive"))
      (node (ref "C26") (pin "1") (pinfunction "1_1") (pintype "passive"))
      (node (ref "C27") (pin "1") (pinfunction "1_1") (pintype "passive"))
      (node (ref "C28") (pin "1") (pinfunction "1_1") (pintype "passive"))
      (node (ref "C29") (pin "2") (pinfunction "2_2") (pintype "passive"))
      (node (ref "C3") (pin "1") (pinfunction "1_1") (pintype "passive"))
      (node (ref "C30") (pin "2") (pinfunction "2_2") (pintype "passive"))
      (node (ref "C31") (pin "1") (pinfunction "1_1") (pintype "passive"))
      (node (ref "C32") (pin "1") (pinfunction "1_1") (pintype "passive"))
      (node (ref "C33") (pin "2") (pinfunction "2_2") (pintype "passive"))
      (node (ref "C34") (pin "2") (pinfunction "2_2") (pintype "passive"))
      (node (ref "C35") (pin "1") (pinfunction "1_1") (pintype "passive"))
      (node (ref "C36") (pin "1") (pinfunction "1_1") (pintype "passive"))
      (node (ref "C37") (pin "2") (pinfunction "2_2") (pintype "passive"))
      (node (ref "C38") (pin "2") (pinfunction "2_2") (pintype "passive"))
      (node (ref "C4") (pin "1") (pinfunction "1_1") (pintype "passive"))
      (node (ref "C5") (pin "1") (pinfunction "1_1") (pintype "passive"))
      (node (ref "C6") (pin "1") (pinfunction "1_1") (pintype "passive"))
      (node (ref "C7") (pin "1") (pinfunction "1_1") (pintype "passive"))
      (node (ref "C8") (pin "1") (pinfunction "1_1") (pintype "passive"))
      (node (ref "C9") (pin "1") (pinfunction "1_1") (pintype "passive"))
      (node (ref "CN1") (pin "1") (pinfunction "P$1_1") (pintype "bidirectional"))
      (node (ref "D1") (pin "-") (pinfunction "-_-") (pintype "passive"))
      (node (ref "D2") (pin "-") (pinfunction "-_-") (pintype "passive"))
      (node (ref "D3") (pin "-") (pinfunction "-_-") (pintype "passive"))
      (node (ref "IC1") (pin "10") (pinfunction "PGND2_10") (pintype "bidirectional"))
      (node (ref "IC1") (pin "18") (pinfunction "GND_18") (pintype "bidirectional"))
      (node (ref "IC1") (pin "3") (pinfunction "PGND_3") (pintype "bidirectional"))
      (node (ref "IC1") (pin "4") (pinfunction "PGND_4") (pintype "bidirectional"))
      (node (ref "IC1") (pin "9") (pinfunction "PGND2_9") (pintype "bidirectional"))
      (node (ref "IC2") (pin "10") (pinfunction "PGND2_10") (pintype "bidirectional"))
      (node (ref "IC2") (pin "18") (pinfunction "GND_18") (pintype "bidirectional"))
      (node (ref "IC2") (pin "3") (pinfunction "PGND_3") (pintype "bidirectional"))
      (node (ref "IC2") (pin "4") (pinfunction "PGND_4") (pintype "bidirectional"))
      (node (ref "IC2") (pin "9") (pinfunction "PGND2_9") (pintype "bidirectional"))
      (node (ref "IC3") (pin "3") (pinfunction "VDD_3") (pintype "bidirectional"))
      (node (ref "IC4") (pin "3") (pinfunction "VDD_3") (pintype "bidirectional"))
      (node (ref "IC5") (pin "11") (pinfunction "VSSA_11") (pintype "bidirectional"))
      (node (ref "IC5") (pin "15") (pinfunction "VREFN_15") (pintype "bidirectional"))
      (node (ref "IC5") (pin "31") (pinfunction "VSS_31") (pintype "bidirectional"))
      (node (ref "IC5") (pin "41") (pinfunction "VSS_41") (pintype "bidirectional"))
      (node (ref "IC5") (pin "55") (pinfunction "VSS_55") (pintype "bidirectional"))
      (node (ref "IC5") (pin "72") (pinfunction "VSS_72") (pintype "bidirectional"))
      (node (ref "IC5") (pin "83") (pinfunction "VSS_83") (pintype "bidirectional"))
      (node (ref "IC5") (pin "97") (pinfunction "VSS_97") (pintype "bidirectional"))
      (node (ref "IC6") (pin "1") (pinfunction "GND_1") (pintype "bidirectional"))
      (node (ref "IC7") (pin "15") (pinfunction "GND_15") (pintype "bidirectional"))
      (node (ref "IR") (pin "3") (pinfunction "GND_3") (pintype "bidirectional"))
      (node (ref "J1") (pin "5") (pinfunction "GND_5") (pintype "bidirectional"))
      (node (ref "J2") (pin "5") (pinfunction "5_5") (pintype "bidirectional"))
      (node (ref "J2") (pin "7") (pinfunction "7_7") (pintype "bidirectional"))
      (node (ref "J3") (pin "3") (pinfunction "3_3") (pintype "bidirectional"))
      (node (ref "J3") (pin "5") (pinfunction "5_5") (pintype "bidirectional"))
      (node (ref "J3") (pin "6") (pinfunction "6_6") (pintype "bidirectional"))
      (node (ref "J3") (pin "G1") (pinfunction "10_G1") (pintype "bidirectional"))
      (node (ref "J3") (pin "G2") (pinfunction "11_G2") (pintype "bidirectional"))
      (node (ref "J4") (pin "10") (pinfunction "10_10") (pintype "bidirectional"))
      (node (ref "J4") (pin "11") (pinfunction "11_11") (pintype "bidirectional"))
      (node (ref "J4") (pin "12") (pinfunction "12_12") (pintype "bidirectional"))
      (node (ref "J4") (pin "13") (pinfunction "13_13") (pintype "bidirectional"))
      (node (ref "J4") (pin "14") (pinfunction "14_14") (pintype "bidirectional"))
      (node (ref "J4") (pin "15") (pinfunction "15_15") (pintype "bidirectional"))
      (node (ref "J4") (pin "9") (pinfunction "9_9") (pintype "bidirectional"))
      (node (ref "J5") (pin "10") (pinfunction "10_10") (pintype "bidirectional"))
      (node (ref "J5") (pin "11") (pinfunction "11_11") (pintype "bidirectional"))
      (node (ref "J5") (pin "12") (pinfunction "12_12") (pintype "bidirectional"))
      (node (ref "J5") (pin "13") (pinfunction "13_13") (pintype "bidirectional"))
      (node (ref "J5") (pin "14") (pinfunction "14_14") (pintype "bidirectional"))
      (node (ref "J5") (pin "15") (pinfunction "15_15") (pintype "bidirectional"))
      (node (ref "J5") (pin "9") (pinfunction "9_9") (pintype "bidirectional"))
      (node (ref "J7") (pin "1") (pinfunction "1_1") (pintype "bidirectional"))
      (node (ref "J8") (pin "4") (pinfunction "4_4") (pintype "bidirectional"))
      (node (ref "SW1") (pin "1") (pinfunction "1_1") (pintype "bidirectional"))
    )
    (net (code "70") (name "Net-(CN1-P$2)") (class "Default")
      (node (ref "CN1") (pin "2") (pinfunction "P$2_2") (pintype "bidirectional"))
      (node (ref "IC5") (pin "6") (pinfunction "P0.26/AD0.3/AOUT/RXD3_6") (pintype "bidirectional"))
    )
    (net (code "71") (name "Net-(CN1-P$3)") (class "Default")
      (node (ref "CN1") (pin "3") (pinfunction "P$3_3") (pintype "bidirectional"))
      (node (ref "IC5") (pin "7") (pinfunction "P0.25/AD0.2/I2SRX_SDA/TXD3_7") (pintype "bidirectional"))
    )
    (net (code "72") (name "Net-(D1-Pad+)") (class "Default")
      (node (ref "D1") (pin "+") (pinfunction "+_+") (pintype "passive"))
      (node (ref "R11") (pin "2") (pinfunction "2_2") (pintype "passive"))
    )
    (net (code "73") (name "Net-(D2-Pad+)") (class "Default")
      (node (ref "D2") (pin "+") (pinfunction "+_+") (pintype "passive"))
      (node (ref "R12") (pin "2") (pinfunction "2_2") (pintype "passive"))
    )
    (net (code "74") (name "Net-(D3-Pad+)") (class "Default")
      (node (ref "D3") (pin "+") (pinfunction "+_+") (pintype "passive"))
      (node (ref "R9") (pin "2") (pinfunction "2_2") (pintype "passive"))
    )
    (net (code "75") (name "Net-(IC5-P0.2{slash}TXD0{slash}AD0.7)") (class "Default")
      (node (ref "IC5") (pin "98") (pinfunction "P0.2/TXD0/AD0.7_98") (pintype "bidirectional"))
      (node (ref "IC7") (pin "11") (pinfunction "DIN1_11") (pintype "input"))
    )
    (net (code "76") (name "Net-(IC5-P0.3{slash}RXD0{slash}AD0.6)") (class "Default")
      (node (ref "IC5") (pin "99") (pinfunction "P0.3/RXD0/AD0.6_99") (pintype "bidirectional"))
      (node (ref "IC7") (pin "12") (pinfunction "ROUT1_12") (pintype "bidirectional"))
    )
    (net (code "77") (name "Net-(IC5-P0.10{slash}TXD2{slash}SDA2{slash}MAT3.0)") (class "Default")
      (node (ref "IC5") (pin "48") (pinfunction "P0.10/TXD2/SDA2/MAT3.0_48") (pintype "bidirectional"))
      (node (ref "J5") (pin "1") (pinfunction "1_1") (pintype "bidirectional"))
      (node (ref "J5") (pin "16") (pinfunction "16_16") (pintype "bidirectional"))
      (node (ref "J6") (pin "1") (pinfunction "1_1") (pintype "bidirectional"))
    )
    (net (code "78") (name "Net-(IC5-P0.18{slash}DCD1{slash}MOSI0{slash}MOSI1)") (class "Default")
      (node (ref "IC5") (pin "60") (pinfunction "P0.18/DCD1/MOSI0/MOSI1_60") (pintype "bidirectional"))
      (node (ref "R10") (pin "1") (pinfunction "1_1") (pintype "passive"))
    )
    (net (code "79") (name "Net-(IC5-P0.29{slash}USB_D+)") (class "Default")
      (node (ref "C15") (pin "2") (pinfunction "2_2") (pintype "passive"))
      (node (ref "IC5") (pin "29") (pinfunction "P0.29/USB_D+_29") (pintype "bidirectional"))
      (node (ref "R2") (pin "1") (pinfunction "1_1") (pintype "passive"))
    )
    (net (code "80") (name "Net-(IC5-P0.30{slash}USB_D-)") (class "Default")
      (node (ref "C14") (pin "2") (pinfunction "2_2") (pintype "passive"))
      (node (ref "IC5") (pin "30") (pinfunction "P0.30/USB_D-_30") (pintype "bidirectional"))
      (node (ref "R3") (pin "1") (pinfunction "1_1") (pintype "passive"))
    )
    (net (code "81") (name "Net-(IC5-P1.30{slash}VBUS{slash}AD0.4)") (class "Default")
      (node (ref "IC5") (pin "21") (pinfunction "P1.30/VBUS/AD0.4_21") (pintype "bidirectional"))
      (node (ref "R5") (pin "1") (pinfunction "1_1") (pintype "passive"))
    )
    (net (code "82") (name "Net-(IC5-P2.10{slash}EINT0N{slash}NMI)") (class "Default")
      (node (ref "IC5") (pin "53") (pinfunction "P2.10/EINT0N/NMI_53") (pintype "bidirectional"))
      (node (ref "R8") (pin "1") (pinfunction "1_1") (pintype "passive"))
      (node (ref "SW1") (pin "2") (pinfunction "2_2") (pintype "bidirectional"))
    )
    (net (code "83") (name "Net-(IC5-P4.28{slash}RX_MCLK{slash}MAT2.0{slash}TXD3)") (class "Default")
      (node (ref "IC5") (pin "82") (pinfunction "P4.28/RX_MCLK/MAT2.0/TXD3_82") (pintype "bidirectional"))
      (node (ref "J8") (pin "1") (pinfunction "1_1") (pintype "bidirectional"))
    )
    (net (code "84") (name "Net-(IC5-P4.29{slash}TX_MCLK{slash}MAT2.1{slash}RXD3)") (class "Default")
      (node (ref "IC5") (pin "85") (pinfunction "P4.29/TX_MCLK/MAT2.1/RXD3_85") (pintype "bidirectional"))
      (node (ref "J8") (pin "5") (pinfunction "5_5") (pintype "bidirectional"))
    )
    (net (code "85") (name "Net-(IC5-X1)") (class "Default")
      (node (ref "C12") (pin "2") (pinfunction "2_2") (pintype "passive"))
      (node (ref "IC5") (pin "22") (pinfunction "X1_22") (pintype "bidirectional"))
      (node (ref "Y1") (pin "1") (pinfunction "1_1") (pintype "passive"))
    )
    (net (code "86") (name "Net-(IC5-X2)") (class "Default")
      (node (ref "C11") (pin "2") (pinfunction "2_2") (pintype "passive"))
      (node (ref "IC5") (pin "23") (pinfunction "X2_23") (pintype "bidirectional"))
      (node (ref "Y1") (pin "2") (pinfunction "2_2") (pintype "passive"))
    )
    (net (code "87") (name "Net-(IC7-C1+)") (class "Default")
      (node (ref "C22") (pin "1") (pinfunction "1_1") (pintype "passive"))
      (node (ref "IC7") (pin "1") (pinfunction "C1+_1") (pintype "bidirectional"))
    )
    (net (code "88") (name "Net-(IC7-C1-)") (class "Default")
      (node (ref "C22") (pin "2") (pinfunction "2_2") (pintype "passive"))
      (node (ref "IC7") (pin "3") (pinfunction "C1-_3") (pintype "bidirectional"))
    )
    (net (code "89") (name "Net-(IC7-C2+)") (class "Default")
      (node (ref "C23") (pin "2") (pinfunction "2_2") (pintype "passive"))
      (node (ref "IC7") (pin "4") (pinfunction "C2+_4") (pintype "bidirectional"))
    )
    (net (code "90") (name "Net-(IC7-C2-)") (class "Default")
      (node (ref "C23") (pin "1") (pinfunction "1_1") (pintype "passive"))
      (node (ref "IC7") (pin "5") (pinfunction "C2-_5") (pintype "bidirectional"))
    )
    (net (code "91") (name "Net-(IC7-V+)") (class "Default")
      (node (ref "C25") (pin "1") (pinfunction "1_1") (pintype "passive"))
      (node (ref "IC7") (pin "2") (pinfunction "V+_2") (pintype "bidirectional"))
    )
    (net (code "92") (name "Net-(IC7-V-)") (class "Default")
      (node (ref "C26") (pin "2") (pinfunction "2_2") (pintype "passive"))
      (node (ref "IC7") (pin "6") (pinfunction "V-_6") (pintype "bidirectional"))
    )
    (net (code "93") (name "Net-(J1-DM)") (class "Default")
      (node (ref "J1") (pin "2") (pinfunction "DM_2") (pintype "bidirectional"))
      (node (ref "R3") (pin "2") (pinfunction "2_2") (pintype "passive"))
    )
    (net (code "94") (name "Net-(J1-DP)") (class "Default")
      (node (ref "J1") (pin "3") (pinfunction "DP_3") (pintype "bidirectional"))
      (node (ref "R1") (pin "1") (pinfunction "1_1") (pintype "passive"))
      (node (ref "R2") (pin "2") (pinfunction "2_2") (pintype "passive"))
    )
    (net (code "95") (name "Net-(Q1-B)") (class "Default")
      (node (ref "Q1") (pin "1") (pinfunction "B_1") (pintype "passive"))
      (node (ref "R4") (pin "2") (pinfunction "2_2") (pintype "passive"))
    )
    (net (code "96") (name "Net-(Q1-C)") (class "Default")
      (node (ref "Q1") (pin "3") (pinfunction "C_3") (pintype "passive"))
      (node (ref "R1") (pin "2") (pinfunction "2_2") (pintype "passive"))
    )
    (net (code "97") (name "VCC") (class "Default")
      (node (ref "C17") (pin "1") (pinfunction "1_1") (pintype "passive"))
      (node (ref "C24") (pin "1") (pinfunction "1_1") (pintype "passive"))
      (node (ref "C35") (pin "2") (pinfunction "2_2") (pintype "passive"))
      (node (ref "C37") (pin "1") (pinfunction "1_1") (pintype "passive"))
      (node (ref "C7") (pin "2") (pinfunction "2_2") (pintype "passive"))
      (node (ref "IC3") (pin "2") (pinfunction "VSS_2") (pintype "bidirectional"))
      (node (ref "IC4") (pin "2") (pinfunction "VSS_2") (pintype "bidirectional"))
      (node (ref "IC6") (pin "3") (pinfunction "IN_3") (pintype "bidirectional"))
      (node (ref "IC7") (pin "16") (pinfunction "VCC_16") (pintype "bidirectional"))
      (node (ref "J1") (pin "1") (pinfunction "VCC_1") (pintype "bidirectional"))
      (node (ref "R5") (pin "2") (pinfunction "2_2") (pintype "passive"))
    )
    (net (code "98") (name "VDD") (class "Default")
      (node (ref "C1") (pin "2") (pinfunction "2_2") (pintype "passive"))
      (node (ref "C10") (pin "2") (pinfunction "2_2") (pintype "passive"))
      (node (ref "C13") (pin "1") (pinfunction "1_1") (pintype "passive"))
      (node (ref "C2") (pin "2") (pinfunction "2_2") (pintype "passive"))
      (node (ref "C28") (pin "2") (pinfunction "2_2") (pintype "passive"))
      (node (ref "C3") (pin "2") (pinfunction "2_2") (pintype "passive"))
      (node (ref "C30") (pin "1") (pinfunction "1_1") (pintype "passive"))
      (node (ref "C32") (pin "2") (pinfunction "2_2") (pintype "passive"))
      (node (ref "C34") (pin "1") (pinfunction "1_1") (pintype "passive"))
      (node (ref "C36") (pin "2") (pinfunction "2_2") (pintype "passive"))
      (node (ref "C38") (pin "1") (pinfunction "1_1") (pintype "passive"))
      (node (ref "C4") (pin "2") (pinfunction "2_2") (pintype "passive"))
      (node (ref "C5") (pin "2") (pinfunction "2_2") (pintype "passive"))
      (node (ref "C6") (pin "2") (pinfunction "2_2") (pintype "passive"))
      (node (ref "C8") (pin "2") (pinfunction "2_2") (pintype "passive"))
      (node (ref "C9") (pin "2") (pinfunction "2_2") (pintype "passive"))
      (node (ref "IC1") (pin "20") (pinfunction "VCC_20") (pintype "bidirectional"))
      (node (ref "IC2") (pin "20") (pinfunction "VCC_20") (pintype "bidirectional"))
      (node (ref "IC5") (pin "10") (pinfunction "VDDA_10") (pintype "bidirectional"))
      (node (ref "IC5") (pin "12") (pinfunction "VREFP_12") (pintype "bidirectional"))
      (node (ref "IC5") (pin "19") (pinfunction "VBAT_19") (pintype "bidirectional"))
      (node (ref "IC5") (pin "28") (pinfunction "VDD3.3V_28") (pintype "bidirectional"))
      (node (ref "IC5") (pin "42") (pinfunction "VDDREG3.3V_42") (pintype "bidirectional"))
      (node (ref "IC5") (pin "54") (pinfunction "VDD3.3V_54") (pintype "bidirectional"))
      (node (ref "IC5") (pin "71") (pinfunction "VDD3.3V_71") (pintype "bidirectional"))
      (node (ref "IC5") (pin "84") (pinfunction "VDDREG3.3V_84") (pintype "bidirectional"))
      (node (ref "IC5") (pin "96") (pinfunction "VDD3.3V_96") (pintype "bidirectional"))
      (node (ref "IC6") (pin "2") (pinfunction "OUT_2") (pintype "bidirectional"))
      (node (ref "IC6") (pin "TER") (pinfunction "OUT_TER") (pintype "bidirectional"))
      (node (ref "IR") (pin "2") (pinfunction "VS_2") (pintype "bidirectional"))
      (node (ref "J4") (pin "1") (pinfunction "1_1") (pintype "bidirectional"))
      (node (ref "J4") (pin "16") (pinfunction "16_16") (pintype "bidirectional"))
      (node (ref "J8") (pin "6") (pinfunction "6_6") (pintype "bidirectional"))
      (node (ref "J8") (pin "8") (pinfunction "8_8") (pintype "bidirectional"))
      (node (ref "Q1") (pin "2") (pinfunction "E_2") (pintype "passive"))
      (node (ref "R18") (pin "2") (pinfunction "2_2") (pintype "passive"))
      (node (ref "R8") (pin "2") (pinfunction "2_2") (pintype "passive"))
    )
    (net (code "99") (name "unconnected-(IC5-NC-Pad13)") (class "Default")
      (node (ref "IC5") (pin "13") (pinfunction "NC_13") (pintype "bidirectional"))
    )
    (net (code "100") (name "unconnected-(IC5-P0.7{slash}I2STX_CLK{slash}SCK1{slash}MAT2.1-Pad78)") (class "Default")
      (node (ref "IC5") (pin "78") (pinfunction "P0.7/I2STX_CLK/SCK1/MAT2.1_78") (pintype "bidirectional"))
    )
    (net (code "101") (name "unconnected-(IC5-P0.19{slash}DSR1{slash}MCICLK{slash}SDA1-Pad59)") (class "Default")
      (node (ref "IC5") (pin "59") (pinfunction "P0.19/DSR1/MCICLK/SDA1_59") (pintype "bidirectional"))
    )
    (net (code "102") (name "unconnected-(IC5-P0.23{slash}AD0.0{slash}I2SRX_CLK{slash}CAP3.0-Pad9)") (class "Default")
      (node (ref "IC5") (pin "9") (pinfunction "P0.23/AD0.0/I2SRX_CLK/CAP3.0_9") (pintype "bidirectional"))
    )
    (net (code "103") (name "unconnected-(IC5-P0.28{slash}SCL0{slash}USB_SCL-Pad24)") (class "Default")
      (node (ref "IC5") (pin "24") (pinfunction "P0.28/SCL0/USB_SCL_24") (pintype "bidirectional"))
    )
    (net (code "104") (name "unconnected-(IC5-P1.15{slash}ENET-RX_CLK-Pad88)") (class "Default")
      (node (ref "IC5") (pin "88") (pinfunction "P1.15/ENET-RX_CLK_88") (pintype "bidirectional"))
    )
    (net (code "105") (name "unconnected-(IC5-P1.16{slash}ENET-MDC-Pad87)") (class "Default")
      (node (ref "IC5") (pin "87") (pinfunction "P1.16/ENET-MDC_87") (pintype "bidirectional"))
    )
    (net (code "106") (name "unconnected-(IC5-P1.17{slash}ENET-MDIO-Pad86)") (class "Default")
      (node (ref "IC5") (pin "86") (pinfunction "P1.17/ENET-MDIO_86") (pintype "bidirectional"))
    )
    (net (code "107") (name "unconnected-(IC5-P1.18{slash}USB_UP{slash}PWM1.1{slash}CAP1.0-Pad32)") (class "Default")
      (node (ref "IC5") (pin "32") (pinfunction "P1.18/USB_UP/PWM1.1/CAP1.0_32") (pintype "bidirectional"))
    )
    (net (code "108") (name "unconnected-(IC5-P1.19{slash}MC0A{slash}USB_PPWR{slash}CAP1.1-Pad33)") (class "Default")
      (node (ref "IC5") (pin "33") (pinfunction "P1.19/MC0A/USB_PPWR/CAP1.1_33") (pintype "bidirectional"))
    )
    (net (code "109") (name "unconnected-(IC5-P1.20{slash}MCFB0{slash}PWM1.2{slash}SCK0-Pad34)") (class "Default")
      (node (ref "IC5") (pin "34") (pinfunction "P1.20/MCFB0/PWM1.2/SCK0_34") (pintype "bidirectional"))
    )
    (net (code "110") (name "unconnected-(IC5-P1.22{slash}MC0B{slash}USB_PWRD{slash}MAT1.0-Pad36)") (class "Default")
      (node (ref "IC5") (pin "36") (pinfunction "P1.22/MC0B/USB_PWRD/MAT1.0_36") (pintype "bidirectional"))
    )
    (net (code "111") (name "unconnected-(IC5-P1.24{slash}MCFB2{slash}PWM1.5{slash}MOSI0-Pad38)") (class "Default")
      (node (ref "IC5") (pin "38") (pinfunction "P1.24/MCFB2/PWM1.5/MOSI0_38") (pintype "bidirectional"))
    )
    (net (code "112") (name "unconnected-(IC5-P1.25{slash}MC1A{slash}MAT1.1-Pad39)") (class "Default")
      (node (ref "IC5") (pin "39") (pinfunction "P1.25/MC1A/MAT1.1_39") (pintype "bidirectional"))
    )
    (net (code "113") (name "unconnected-(IC5-P1.28{slash}MC2A{slash}PCAP1.0{slash}MAT0.0-Pad44)") (class "Default")
      (node (ref "IC5") (pin "44") (pinfunction "P1.28/MC2A/PCAP1.0/MAT0.0_44") (pintype "bidirectional"))
    )
    (net (code "114") (name "unconnected-(IC5-P1.29{slash}MC2B{slash}PCAP1.1{slash}MAT0.1-Pad45)") (class "Default")
      (node (ref "IC5") (pin "45") (pinfunction "P1.29/MC2B/PCAP1.1/MAT0.1_45") (pintype "bidirectional"))
    )
    (net (code "115") (name "unconnected-(IC5-P1.31{slash}SCK1{slash}AD0.5-Pad20)") (class "Default")
      (node (ref "IC5") (pin "20") (pinfunction "P1.31/SCK1/AD0.5_20") (pintype "bidirectional"))
    )
    (net (code "116") (name "unconnected-(IC5-P2.2{slash}PWM1.3{slash}CTS1{slash}TRACEDATA3-Pad73)") (class "Default")
      (node (ref "IC5") (pin "73") (pinfunction "P2.2/PWM1.3/CTS1/TRACEDATA3_73") (pintype "bidirectional"))
    )
    (net (code "117") (name "unconnected-(IC5-P2.11{slash}EINT1N{slash}I2STX_CLK-Pad52)") (class "Default")
      (node (ref "IC5") (pin "52") (pinfunction "P2.11/EINT1N/I2STX_CLK_52") (pintype "bidirectional"))
    )
    (net (code "118") (name "unconnected-(IC5-P2.12{slash}EINT2N{slash}I2STX_WS-Pad51)") (class "Default")
      (node (ref "IC5") (pin "51") (pinfunction "P2.12/EINT2N/I2STX_WS_51") (pintype "bidirectional"))
    )
    (net (code "119") (name "unconnected-(IC5-P2.13{slash}EINT3N{slash}I2STX_SDA-Pad50)") (class "Default")
      (node (ref "IC5") (pin "50") (pinfunction "P2.13/EINT3N/I2STX_SDA_50") (pintype "bidirectional"))
    )
    (net (code "120") (name "unconnected-(IC5-RSTOUTN-Pad14)") (class "Default")
      (node (ref "IC5") (pin "14") (pinfunction "RSTOUTN_14") (pintype "bidirectional"))
    )
    (net (code "121") (name "unconnected-(IC5-RTCX1-Pad16)") (class "Default")
      (node (ref "IC5") (pin "16") (pinfunction "RTCX1_16") (pintype "bidirectional"))
    )
    (net (code "122") (name "unconnected-(IC5-RTCX2-Pad18)") (class "Default")
      (node (ref "IC5") (pin "18") (pinfunction "RTCX2_18") (pintype "bidirectional"))
    )
    (net (code "123") (name "unconnected-(J1-GND-Pad6)") (class "Default")
      (node (ref "J1") (pin "6") (pinfunction "GND_6") (pintype "bidirectional"))
    )
    (net (code "124") (name "unconnected-(J1-GND-Pad7)") (class "Default")
      (node (ref "J1") (pin "7") (pinfunction "GND_7") (pintype "bidirectional"))
    )
    (net (code "125") (name "unconnected-(J1-ID-Pad4)") (class "Default")
      (node (ref "J1") (pin "4") (pinfunction "ID_4") (pintype "bidirectional"))
    )
    (net (code "126") (name "unconnected-(J2-10-PadG1)") (class "Default")
      (node (ref "J2") (pin "G1") (pinfunction "10_G1") (pintype "bidirectional"))
    )
    (net (code "127") (name "unconnected-(J2-11-PadG2)") (class "Default")
      (node (ref "J2") (pin "G2") (pinfunction "11_G2") (pintype "bidirectional"))
    )
    (net (code "128") (name "unconnected-(J2-Pad4)") (class "Default")
      (node (ref "J2") (pin "4") (pinfunction "4_4") (pintype "bidirectional"))
    )
    (net (code "129") (name "unconnected-(J2-Pad8)") (class "Default")
      (node (ref "J2") (pin "8") (pinfunction "8_8") (pintype "bidirectional"))
    )
    (net (code "130") (name "unconnected-(J2-Pad9)") (class "Default")
      (node (ref "J2") (pin "9") (pinfunction "9_9") (pintype "bidirectional"))
    )
    (net (code "131") (name "unconnected-(J3-Pad4)") (class "Default")
      (node (ref "J3") (pin "4") (pinfunction "4_4") (pintype "bidirectional"))
    )
    (net (code "132") (name "unconnected-(J3-Pad9)") (class "Default")
      (node (ref "J3") (pin "9") (pinfunction "9_9") (pintype "bidirectional"))
    )
  )
)
